# SerialToUSB.net
KiCad netlist of a schematic drawn in Altium Designer
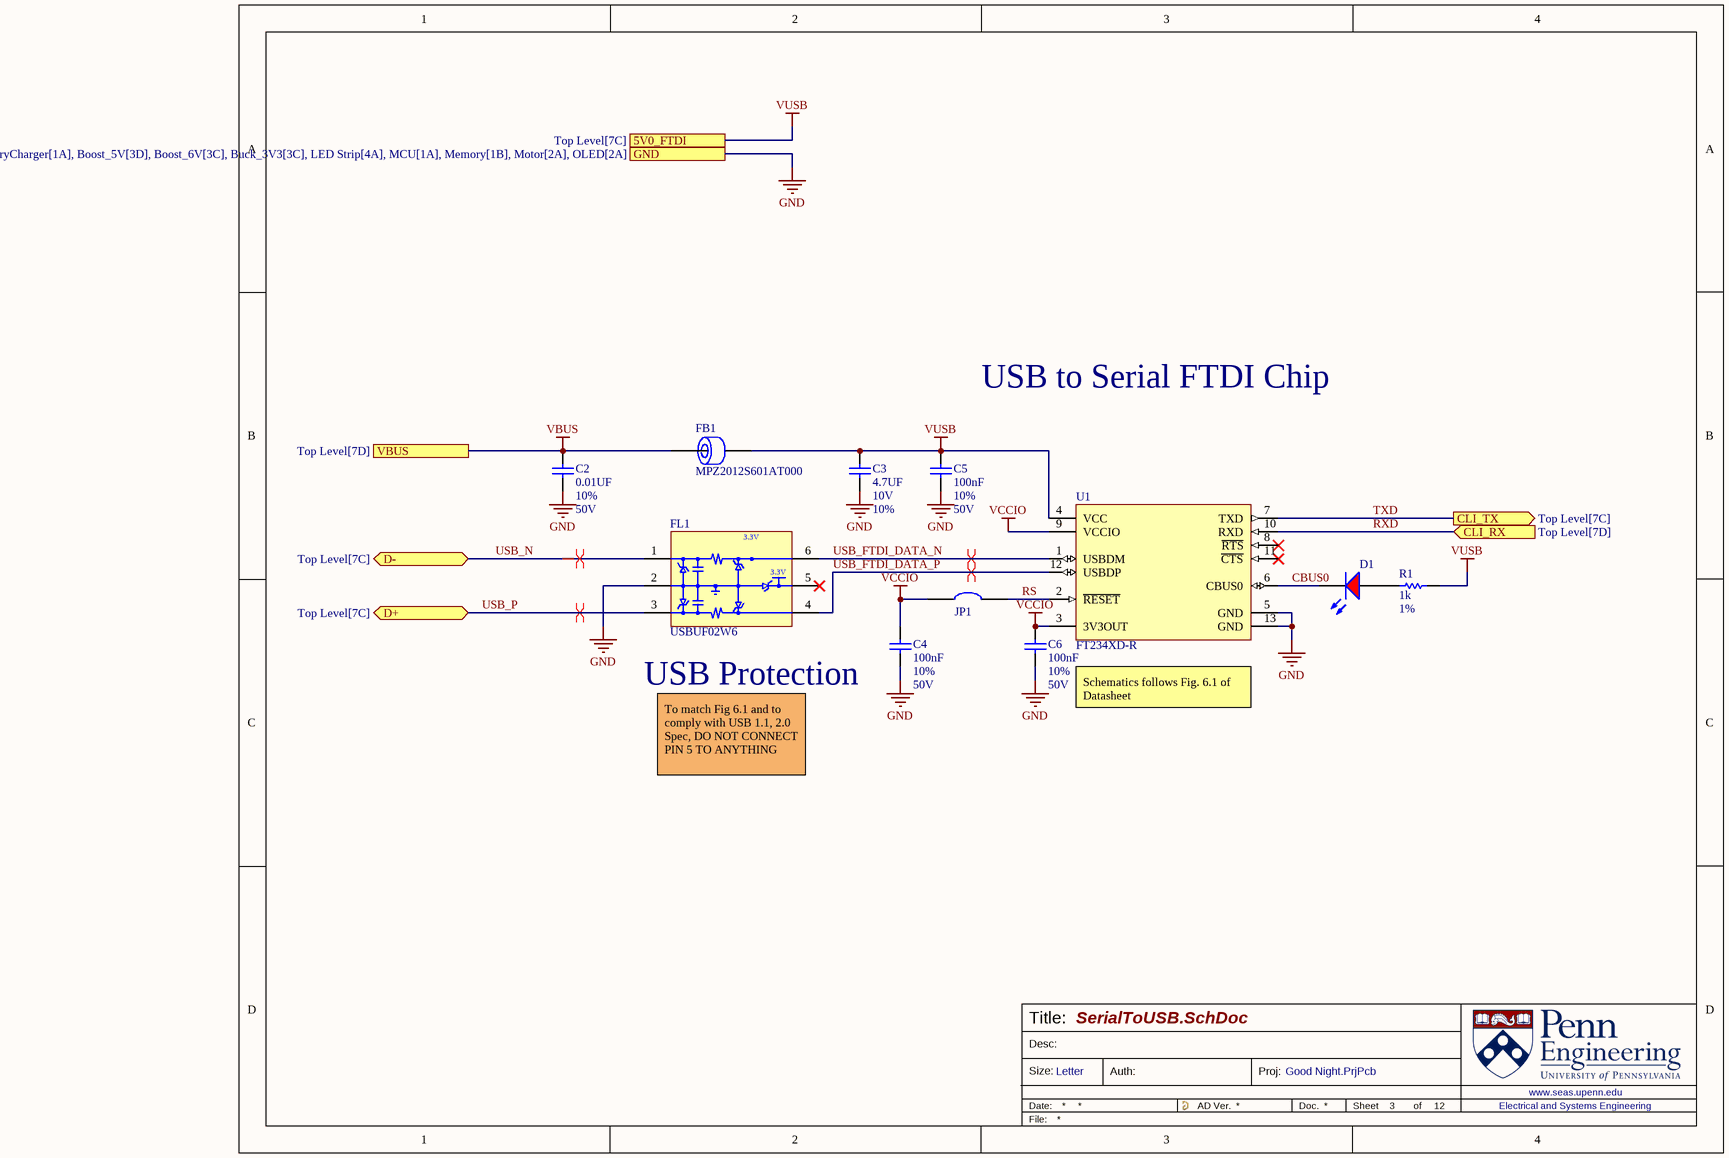
[diagram p0: SerialToUSB.SchDoc]

(export (version "E")
  (design (tool "Eeschema 10.0.6"))
  (components
    (comp (ref "C2")
      (value "0.01UF")
      (footprint "0603_CAP")
      (description "Capacitor Surface Mount 0603 Footprint 0.01UF 50V 10% Tolerance Ceramic X7R")
      (fields
        (field (name "TOLERANCE") "10%")
        (field (name "JLCPCB PART #") "C57112")
        (field (name "VOLTAGE") "50V")
        (field (name "MANUFACTURER") "Various")
      )
      (libsource (lib "University of Pennsylvania (ESE)") (part "cap"))
    )
    (comp (ref "C3")
      (value "4.7UF")
      (footprint "0805_CAP")
      (description "Capacitor Surface Mount 0805 Footprint 4.7UF 10V 10% Tolerance Ceramic X7R")
      (fields
        (field (name "MANUFACTURER") "Various")
        (field (name "VOLTAGE") "10V")
        (field (name "TOLERANCE") "10%")
        (field (name "Comment") "CAP 0805 4.7UF 10V 10% X7R")
      )
      (libsource (lib "University of Pennsylvania (ESE)") (part "cap"))
    )
    (comp (ref "C4")
      (value "100nF")
      (footprint "0603_CAP")
      (description "Capacitor Surface Mount 0603 Footprint 0.1UF 50V 10% Tolerance Ceramic X7R 100nF")
      (fields
        (field (name "TOLERANCE") "10%")
        (field (name "JLCPCB PART #") "C14663")
        (field (name "MANUFACTURER") "Various")
        (field (name "VOLTAGE") "50V")
      )
      (libsource (lib "University of Pennsylvania (ESE)") (part "cap"))
    )
    (comp (ref "C5")
      (value "100nF")
      (footprint "0603_CAP")
      (description "Capacitor Surface Mount 0603 Footprint 0.1UF 50V 10% Tolerance Ceramic X7R 100nF")
      (fields
        (field (name "TOLERANCE") "10%")
        (field (name "JLCPCB PART #") "C14663")
        (field (name "MANUFACTURER") "Various")
        (field (name "VOLTAGE") "50V")
      )
      (libsource (lib "University of Pennsylvania (ESE)") (part "cap"))
    )
    (comp (ref "C6")
      (value "100nF")
      (footprint "0603_CAP")
      (description "Capacitor Surface Mount 0603 Footprint 0.1UF 50V 10% Tolerance Ceramic X7R 100nF")
      (fields
        (field (name "TOLERANCE") "10%")
        (field (name "JLCPCB PART #") "C14663")
        (field (name "MANUFACTURER") "Various")
        (field (name "VOLTAGE") "50V")
      )
      (libsource (lib "University of Pennsylvania (ESE)") (part "cap"))
    )
    (comp (ref "D1")
      (value "LSM0805412V")
      (footprint "LED_0805_RED")
      (description "Single Color LED, RED, 0805")
      (libsource (lib "University of Pennsylvania (ESE)") (part "LED-RED-AK-2"))
    )
    (comp (ref "FB1")
      (value "MPZ2012S601AT000")
      (footprint "FP-MPZ2012-MFG (0805)")
      (description "600 Ohms @ 100 MHz 1 Power Line Ferrite Bead 0805 (2012 Metric) 2A 100mOhm")
      (libsource (lib "University of Pennsylvania (ESE)") (part "Ferrite Bead"))
    )
    (comp (ref "FL1")
      (value "USBUF02W6")
      (footprint "SOT-363-6-ST")
      (libsource (lib "University of Pennsylvania (ESE)") (part "USBUF02W6"))
    )
    (comp (ref "JP1")
      (value "0603 link")
      (footprint "0603_JP_RES")
      (description "0O link, SMD, 0603, Solder Bridge Option")
      (fields (field (name "MANUFACTURER") "Generic") (field (name "SOURCE") "Shunts and Jumpers.SchLib"))
      (libsource (lib "University of Pennsylvania (ESE)") (part "CMP-ROOT-0007-1"))
    )
    (comp (ref "R1")
      (value "1k")
      (footprint "0603_RES")
      (description "Resistor Surface Mount, 1K Ohms, 0603 Footprint, 1% Tolerance 0.1W")
      (fields
        (field (name "JLCPCB PART #") "C21190")
        (field (name "MANUFACTURER") "Various")
        (field (name "TOLERANCE") "1%")
      )
      (libsource (lib "University of Pennsylvania (ESE)") (part "res"))
    )
    (comp (ref "U1")
      (value "FT234XD-R")
      (footprint "FP-DFN-12-MFG")
      (description "USB Bridge, USB to UART USB 2.0 UART Interface 12-DFN (3x3)")
      (libsource (lib "University of Pennsylvania (ESE)") (part "FT234-Symbol"))
    )
  )
  (nets
    (net (code "1") (name "/CBUS0") (class "Default")
      (node (ref "D1") (pin "K") (pinfunction "K_K") (pintype "passive"))
      (node (ref "U1") (pin "6") (pinfunction "CBUS0_6") (pintype "bidirectional"))
    )
    (net (code "2") (name "/RS") (class "Default")
      (node (ref "JP1") (pin "2") (pinfunction "2_2") (pintype "passive"))
      (node (ref "U1") (pin "2") (pinfunction "~{RESET}_2") (pintype "input"))
    )
    (net (code "3") (name "/RXD") (class "Default")
      (node (ref "U1") (pin "10") (pinfunction "RXD_10") (pintype "input"))
    )
    (net (code "4") (name "/TXD") (class "Default")
      (node (ref "U1") (pin "7") (pinfunction "TXD_7") (pintype "output"))
    )
    (net (code "5") (name "/USB_FTDI_DATA_N") (class "Default")
      (node (ref "FL1") (pin "6") (pinfunction "D4_6") (pintype "passive"))
      (node (ref "U1") (pin "1") (pinfunction "USBDM_1") (pintype "bidirectional"))
    )
    (net (code "6") (name "/USB_FTDI_DATA_P") (class "Default")
      (node (ref "FL1") (pin "4") (pinfunction "D3_4") (pintype "passive"))
      (node (ref "U1") (pin "12") (pinfunction "USBDP_12") (pintype "bidirectional"))
    )
    (net (code "7") (name "/USB_N") (class "Default")
      (node (ref "FL1") (pin "1") (pinfunction "D1_1") (pintype "passive"))
    )
    (net (code "8") (name "/USB_P") (class "Default")
      (node (ref "FL1") (pin "3") (pinfunction "D2_3") (pintype "passive"))
    )
    (net (code "9") (name "GND") (class "Default")
      (node (ref "C2") (pin "1") (pinfunction "1_1") (pintype "passive"))
      (node (ref "C3") (pin "1") (pinfunction "1_1") (pintype "passive"))
      (node (ref "C4") (pin "1") (pinfunction "1_1") (pintype "passive"))
      (node (ref "C5") (pin "1") (pinfunction "1_1") (pintype "passive"))
      (node (ref "C6") (pin "1") (pinfunction "1_1") (pintype "passive"))
      (node (ref "FL1") (pin "2") (pinfunction "GND_2") (pintype "power_in"))
      (node (ref "U1") (pin "13") (pinfunction "GND_13") (pintype "power_in"))
      (node (ref "U1") (pin "5") (pinfunction "GND_5") (pintype "power_in"))
    )
    (net (code "10") (name "Net-(D1-PadA)") (class "Default")
      (node (ref "D1") (pin "A") (pinfunction "A_A") (pintype "passive"))
      (node (ref "R1") (pin "1") (pinfunction "1_1") (pintype "passive"))
    )
    (net (code "11") (name "VBUS") (class "Default")
      (node (ref "C2") (pin "2") (pinfunction "2_2") (pintype "passive"))
      (node (ref "FB1") (pin "1") (pinfunction "1_1") (pintype "passive"))
    )
    (net (code "12") (name "VCCIO") (class "Default")
      (node (ref "C4") (pin "2") (pinfunction "2_2") (pintype "passive"))
      (node (ref "C6") (pin "2") (pinfunction "2_2") (pintype "passive"))
      (node (ref "JP1") (pin "1") (pinfunction "1_1") (pintype "passive"))
      (node (ref "U1") (pin "3") (pinfunction "3V3OUT_3") (pintype "power_in"))
      (node (ref "U1") (pin "9") (pinfunction "VCCIO_9") (pintype "power_in"))
    )
    (net (code "13") (name "VUSB") (class "Default")
      (node (ref "C3") (pin "2") (pinfunction "2_2") (pintype "passive"))
      (node (ref "C5") (pin "2") (pinfunction "2_2") (pintype "passive"))
      (node (ref "FB1") (pin "2") (pinfunction "2_2") (pintype "passive"))
      (node (ref "R1") (pin "2") (pinfunction "2_2") (pintype "passive"))
      (node (ref "U1") (pin "4") (pinfunction "VCC_4") (pintype "power_in"))
    )
    (net (code "14") (name "unconnected-(FL1-3.3_V-Pad5)") (class "Default")
      (node (ref "FL1") (pin "5") (pinfunction "3.3_V_5") (pintype "power_in+no_connect"))
    )
    (net (code "15") (name "unconnected-(U1-~{CTS}-Pad11)") (class "Default")
      (node (ref "U1") (pin "11") (pinfunction "~{CTS}_11") (pintype "input+no_connect"))
    )
    (net (code "16") (name "unconnected-(U1-~{RTS}-Pad8)") (class "Default")
      (node (ref "U1") (pin "8") (pinfunction "~{RTS}_8") (pintype "input+no_connect"))
    )
  )
)
